# SAMV71_Xplained_Ultra_CAN.net
KiCad netlist of a schematic drawn in Altium Designer
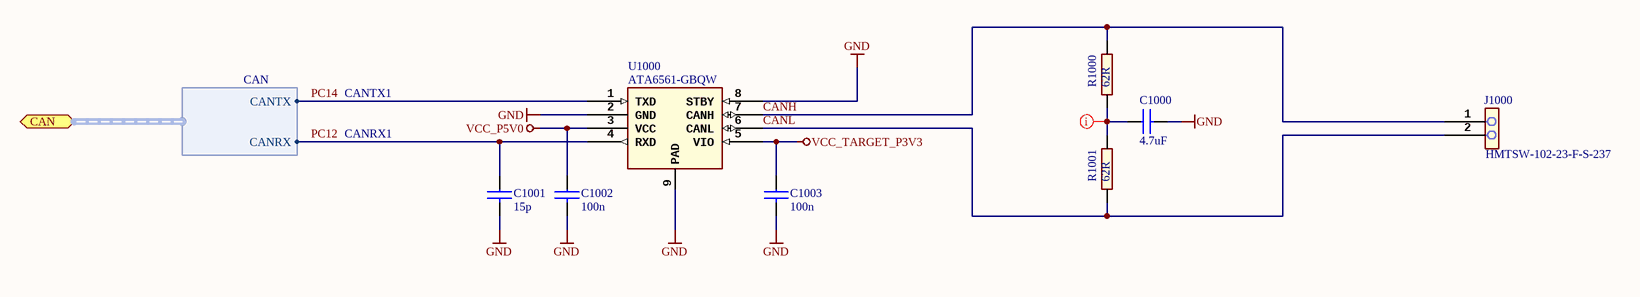
[diagram p0: SAMV71_Xplained_Ultra_CAN.SchDoc]

(export (version "E")
  (design (tool "Eeschema 10.0.6"))
  (components
    (comp (ref "C1000")
      (value "4.7uF")
      (footprint "AP1-00003")
      (description "Ceramic capacitor, SMD 0805, X5R, 25V, ±10 %")
      (fields (field (name "TOLERANCE") "Â±10%") (field (name "MANUFACTURER") "Murata"))
      (libsource (lib "AltiumDbLib") (part "CAP-NONPOL"))
    )
    (comp (ref "C1001")
      (value "15p")
      (footprint "AP1-00001")
      (description "Ceramic capacitor, SMD 0402, NP0, 50V, +/-5%")
      (fields (field (name "TOLERANCE") "50V, +/-5%") (field (name "MANUFACTURER") "AVX"))
      (libsource (lib "AltiumDbLib") (part "CAP-NONPOL"))
    )
    (comp (ref "C1002")
      (value "100n")
      (footprint "AP1-00001")
      (description "Ceramic capacitor, SMD 0402, X7R, 16V, +/-10%")
      (fields (field (name "TOLERANCE") "16V, +/-10%") (field (name "MANUFACTURER") "Kemet"))
      (libsource (lib "AltiumDbLib") (part "CAP-NONPOL"))
    )
    (comp (ref "C1003")
      (value "100n")
      (footprint "AP1-00001")
      (description "Ceramic capacitor, SMD 0402, X7R, 16V, +/-10%")
      (fields (field (name "TOLERANCE") "16V, +/-10%") (field (name "MANUFACTURER") "Kemet"))
      (libsource (lib "AltiumDbLib") (part "CAP-NONPOL"))
    )
    (comp (ref "J1000")
      (value "HMTSW-102-23-F-S-237")
      (footprint "AP8-00733")
      (description "1x2 pin header, 2.54mm pitch, Pin-in-Paste THM")
      (fields (field (name "MANUFACTURER") "SAMTEC"))
      (libsource (lib "AltiumDbLib") (part "HEADER 1x2"))
    )
    (comp (ref "R1000")
      (value "62R")
      (footprint "AP2-00008")
      (description "Thick film resistor, SMD 1210, 0.5W, 1%")
      (fields (field (name "TOLERANCE") "1%") (field (name "MANUFACTURER") "vishay"))
      (libsource (lib "AltiumDbLib") (part "R2"))
    )
    (comp (ref "R1001")
      (value "62R")
      (footprint "AP2-00008")
      (description "Thick film resistor, SMD 1210, 0.5W, 1%")
      (fields (field (name "TOLERANCE") "1%") (field (name "MANUFACTURER") "vishay"))
      (libsource (lib "AltiumDbLib") (part "R2"))
    )
    (comp (ref "U1000")
      (value "ATA6561-GBQW")
      (footprint "AP6-00407")
      (description "5Mbit/s CAN Trasceiver,VCC = 5V, VIO = 2.8-5V, 3x3 mm VDFN8")
      (fields (field (name "MANUFACTURER") "ATMEL"))
      (libsource (lib "AltiumDbLib") (part "ATA6561"))
    )
  )
  (nets
    (net (code "2") (name "/CANH") (class "Default")
      (node (ref "J1000") (pin "1") (pinfunction "1_1") (pintype "passive"))
      (node (ref "R1000") (pin "2") (pinfunction "2_2") (pintype "passive"))
      (node (ref "U1000") (pin "7") (pinfunction "CANH_7") (pintype "bidirectional"))
    )
    (net (code "3") (name "/CANL") (class "Default")
      (node (ref "J1000") (pin "2") (pinfunction "2_2") (pintype "passive"))
      (node (ref "R1001") (pin "1") (pinfunction "1_1") (pintype "passive"))
      (node (ref "U1000") (pin "6") (pinfunction "CANL_6") (pintype "bidirectional"))
    )
    (net (code "4") (name "/PC12") (class "Default")
      (node (ref "C1001") (pin "1") (pinfunction "1_1") (pintype "passive"))
      (node (ref "U1000") (pin "4") (pinfunction "RXD_4") (pintype "output"))
    )
    (net (code "5") (name "/PC14") (class "Default")
      (node (ref "U1000") (pin "1") (pinfunction "TXD_1") (pintype "input"))
    )
    (net (code "7") (name "GND") (class "Default")
      (node (ref "C1000") (pin "2") (pinfunction "2_2") (pintype "passive"))
      (node (ref "C1001") (pin "2") (pinfunction "2_2") (pintype "passive"))
      (node (ref "C1002") (pin "2") (pinfunction "2_2") (pintype "passive"))
      (node (ref "C1003") (pin "2") (pinfunction "2_2") (pintype "passive"))
      (node (ref "U1000") (pin "2") (pinfunction "GND_2") (pintype "power_in"))
      (node (ref "U1000") (pin "8") (pinfunction "STBY_8") (pintype "input"))
      (node (ref "U1000") (pin "9") (pinfunction "PAD_9") (pintype "power_in"))
    )
    (net (code "8") (name "Net-(C1000-Pad1)") (class "Default")
      (node (ref "C1000") (pin "1") (pinfunction "1_1") (pintype "passive"))
      (node (ref "R1000") (pin "1") (pinfunction "1_1") (pintype "passive"))
      (node (ref "R1001") (pin "2") (pinfunction "2_2") (pintype "passive"))
    )
    (net (code "9") (name "VCC_P5V0") (class "Default")
      (node (ref "C1002") (pin "1") (pinfunction "1_1") (pintype "passive"))
      (node (ref "U1000") (pin "3") (pinfunction "VCC_3") (pintype "power_in"))
    )
    (net (code "10") (name "VCC_TARGET_P3V3") (class "Default")
      (node (ref "C1003") (pin "1") (pinfunction "1_1") (pintype "passive"))
      (node (ref "U1000") (pin "5") (pinfunction "VIO_5") (pintype "input"))
    )
  )
)
